# Sheet1.net
KiCad netlist of a schematic drawn in Altium Designer
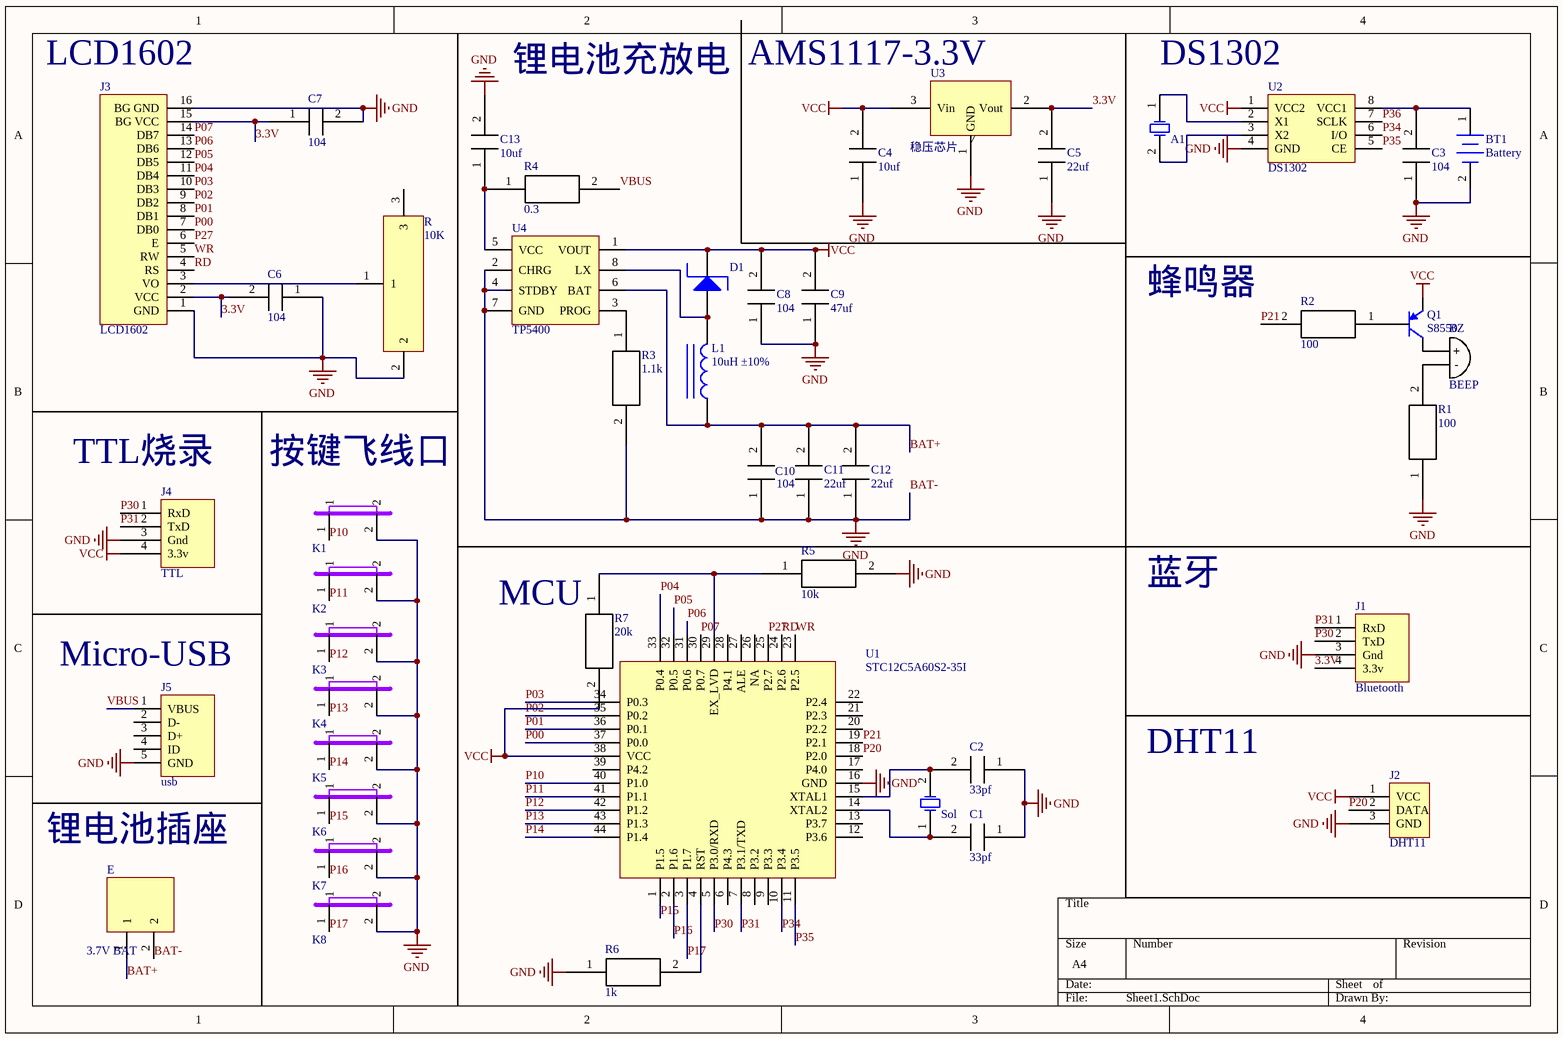
[diagram p0: Sheet1.SchDoc]

(export (version "E")
  (design (tool "Eeschema 10.0.6"))
  (components
    (comp (ref "A1")
      (value "CrystalOscillator")
      (footprint "3*8圆柱晶振")
      (description "晶振")
      (libsource (lib "Schlib1") (part "XTAL"))
    )
    (comp (ref "BT1")
      (value "Battery")
      (footprint "CR1220_A")
      (description "Multicell Battery")
      (fields (field (name "PUBLISHER") "Altium Limited"))
      (libsource (lib "Schlib1") (part "Battery"))
    )
    (comp (ref "BZ")
      (value "BEEP")
      (footprint "BEEP 6.6x12x8.5")
      (description "蜂鸣器")
      (libsource (lib "Schlib1") (part "BEEP"))
    )
    (comp (ref "C1")
      (value "33pf")
      (footprint "C 0805_M")
      (description "电容")
      (libsource (lib "Schlib1") (part "电容"))
    )
    (comp (ref "C2")
      (value "33pf")
      (footprint "C 0805_M")
      (description "电容")
      (libsource (lib "Schlib1") (part "电容"))
    )
    (comp (ref "C3")
      (value "104")
      (footprint "C 0805_M")
      (description "电容")
      (libsource (lib "Schlib1") (part "电容"))
    )
    (comp (ref "C4")
      (value "10uf")
      (footprint "C 0805_M")
      (description "电容")
      (libsource (lib "Schlib1") (part "电容"))
    )
    (comp (ref "C5")
      (value "22uf")
      (footprint "C 0805_M")
      (description "电容")
      (libsource (lib "Schlib1") (part "电容"))
    )
    (comp (ref "C6")
      (value "104")
      (footprint "C 0805_M")
      (description "电容")
      (libsource (lib "Schlib1") (part "电容"))
    )
    (comp (ref "C7")
      (value "104")
      (footprint "C 0805_M")
      (description "电容")
      (libsource (lib "Schlib1") (part "电容"))
    )
    (comp (ref "C8")
      (value "104")
      (footprint "C 0805_M")
      (description "电容")
      (libsource (lib "Schlib1") (part "电容"))
    )
    (comp (ref "C9")
      (value "47uf")
      (footprint "C 0805_M")
      (description "电容")
      (libsource (lib "Schlib1") (part "电容"))
    )
    (comp (ref "C10")
      (value "104")
      (footprint "C 0805_M")
      (description "电容")
      (libsource (lib "Schlib1") (part "电容"))
    )
    (comp (ref "C11")
      (value "22uf")
      (footprint "C 0805_M")
      (description "电容")
      (libsource (lib "Schlib1") (part "电容"))
    )
    (comp (ref "C12")
      (value "22uf")
      (footprint "C 0805_M")
      (description "电容")
      (libsource (lib "Schlib1") (part "电容"))
    )
    (comp (ref "C13")
      (value "10uf")
      (footprint "C 0805_M")
      (description "电容")
      (libsource (lib "Schlib1") (part "电容"))
    )
    (comp (ref "D1")
      (value "B5819W  SL")
      (footprint "SMB")
      (description "肖特基二极管")
      (libsource (lib "Schlib1") (part "SOD-123 B5819W  SL"))
    )
    (comp (ref "E")
      (value "3.7V BAT")
      (footprint "XH2.54-LI-2P")
      (description "电源")
      (libsource (lib "Schlib1") (part "E"))
    )
    (comp (ref "J1")
      (value "Bluetooth")
      (footprint "HDR2.54-M-LI-4P")
      (description "蓝牙")
      (libsource (lib "Schlib1") (part "BT06-B"))
    )
    (comp (ref "J2") (value "DHT11") (footprint "HDR2.54-M-LI-3P") (libsource (lib "Schlib1") (part "DHT11")))
    (comp (ref "J3") (value "LCD1602") (footprint "LCD-1602") (libsource (lib "Schlib1") (part "LCD1602")))
    (comp (ref "J4")
      (value "TTL")
      (footprint "HDR2.54-LI-4P")
      (description "蓝牙")
      (libsource (lib "Schlib1") (part "BT06-B"))
    )
    (comp (ref "J5") (value "usb") (footprint "USB-micro_C") (libsource (lib "Schlib1") (part "usb")))
    (comp (ref "K1")
      (value "key")
      (footprint "飞线口")
      (description "按键")
      (libsource (lib "Schlib1") (part "key"))
    )
    (comp (ref "K2")
      (value "key")
      (footprint "飞线口")
      (description "按键")
      (libsource (lib "Schlib1") (part "key"))
    )
    (comp (ref "K3")
      (value "key")
      (footprint "飞线口")
      (description "按键")
      (libsource (lib "Schlib1") (part "key"))
    )
    (comp (ref "K4")
      (value "key")
      (footprint "飞线口")
      (description "按键")
      (libsource (lib "Schlib1") (part "key"))
    )
    (comp (ref "K5")
      (value "key")
      (footprint "飞线口")
      (description "按键")
      (libsource (lib "Schlib1") (part "key"))
    )
    (comp (ref "K6")
      (value "key")
      (footprint "飞线口")
      (description "按键")
      (libsource (lib "Schlib1") (part "key"))
    )
    (comp (ref "K7")
      (value "key")
      (footprint "飞线口")
      (description "按键")
      (libsource (lib "Schlib1") (part "key"))
    )
    (comp (ref "K8")
      (value "key")
      (footprint "飞线口")
      (description "按键")
      (libsource (lib "Schlib1") (part "key"))
    )
    (comp (ref "L1")
      (value "10uH ±10%")
      (footprint "0805_L")
      (description "贴片电感")
      (libsource (lib "Schlib1") (part "0805 10uH 10%"))
    )
    (comp (ref "Q1")
      (value "S8550")
      (footprint "SOT23")
      (description "Discrete PNP Bipolar Transistor")
      (fields (field (name "PARTNUMBER") "S8550") (field (name "PUBLISHER") "Altium Limited"))
      (libsource (lib "Schlib1") (part "PNP S8550"))
    )
    (comp (ref "R")
      (value "10K")
      (footprint "可变电阻")
      (description "电位器")
      (libsource (lib "Schlib1") (part "3296"))
    )
    (comp (ref "R1")
      (value "100")
      (footprint "0805R")
      (description "电阻")
      (libsource (lib "Schlib1") (part "电阻"))
    )
    (comp (ref "R2")
      (value "100")
      (footprint "0805R")
      (description "电阻")
      (libsource (lib "Schlib1") (part "电阻"))
    )
    (comp (ref "R3")
      (value "1.1k")
      (footprint "0805R")
      (description "电阻")
      (libsource (lib "Schlib1") (part "电阻"))
    )
    (comp (ref "R4")
      (value "0.3")
      (footprint "0805R")
      (description "电阻")
      (libsource (lib "Schlib1") (part "电阻"))
    )
    (comp (ref "R5")
      (value "10k")
      (footprint "0805R")
      (description "电阻")
      (libsource (lib "Schlib1") (part "电阻"))
    )
    (comp (ref "R6")
      (value "1k")
      (footprint "0805R")
      (description "电阻")
      (libsource (lib "Schlib1") (part "电阻"))
    )
    (comp (ref "R7")
      (value "20k")
      (footprint "0805R")
      (description "电阻")
      (libsource (lib "Schlib1") (part "电阻"))
    )
    (comp (ref "Sol")
      (value "CrystalOscillator")
      (footprint "OSC HC-49S")
      (description "晶振")
      (libsource (lib "Schlib1") (part "XTAL"))
    )
    (comp (ref "U1")
      (value "STC12C5A60S2-35I")
      (footprint "LQFP44-10*10")
      (description "MCU")
      (libsource (lib "Schlib1") (part "STC12C5A60S2-35I"))
    )
    (comp (ref "U2")
      (value "DS1302")
      (footprint "DIP8")
      (description "DS1302时钟芯片")
      (libsource (lib "Schlib1") (part "DS1302"))
    )
    (comp (ref "U3") (value "稳压芯片") (footprint "SOT-223") (libsource (lib "Schlib1") (part "AMS1117")))
    (comp (ref "U4")
      (value "TP5400")
      (footprint "SOP8")
      (description "电池管理芯片")
      (libsource (lib "Schlib1") (part "TP5400"))
    )
  )
  (nets
    (net (code "1") (name "/3.3V") (class "Default")
      (node (ref "C5") (pin "2") (pinfunction "2_2") (pintype "passive"))
      (node (ref "C6") (pin "2") (pinfunction "2_2") (pintype "passive"))
      (node (ref "C7") (pin "1") (pinfunction "1_1") (pintype "passive"))
      (node (ref "J1") (pin "4") (pinfunction "3.3v_4") (pintype "passive"))
      (node (ref "J3") (pin "15") (pinfunction "BG_VCC_15") (pintype "passive"))
      (node (ref "J3") (pin "2") (pinfunction "VCC_2") (pintype "passive"))
      (node (ref "U3") (pin "2") (pinfunction "Vout_2") (pintype "passive"))
    )
    (net (code "2") (name "/BAT+") (class "Default")
      (node (ref "C10") (pin "2") (pinfunction "2_2") (pintype "passive"))
      (node (ref "C11") (pin "2") (pinfunction "2_2") (pintype "passive"))
      (node (ref "C12") (pin "2") (pinfunction "2_2") (pintype "passive"))
      (node (ref "E") (pin "1") (pinfunction "1_1") (pintype "passive"))
      (node (ref "L1") (pin "1") (pinfunction "1_1") (pintype "passive"))
      (node (ref "U4") (pin "6") (pinfunction "BAT_6") (pintype "passive"))
    )
    (net (code "3") (name "/P00") (class "Default")
      (node (ref "J3") (pin "7") (pinfunction "DB0_7") (pintype "passive"))
      (node (ref "U1") (pin "37") (pinfunction "P0.0_37") (pintype "passive"))
    )
    (net (code "4") (name "/P01") (class "Default")
      (node (ref "J3") (pin "8") (pinfunction "DB1_8") (pintype "passive"))
      (node (ref "U1") (pin "36") (pinfunction "P0.1_36") (pintype "passive"))
    )
    (net (code "5") (name "/P02") (class "Default")
      (node (ref "J3") (pin "9") (pinfunction "DB2_9") (pintype "passive"))
      (node (ref "U1") (pin "35") (pinfunction "P0.2_35") (pintype "passive"))
    )
    (net (code "6") (name "/P03") (class "Default")
      (node (ref "J3") (pin "10") (pinfunction "DB3_10") (pintype "passive"))
      (node (ref "U1") (pin "34") (pinfunction "P0.3_34") (pintype "passive"))
    )
    (net (code "7") (name "/P04") (class "Default")
      (node (ref "J3") (pin "11") (pinfunction "DB4_11") (pintype "passive"))
      (node (ref "U1") (pin "33") (pinfunction "P0.4_33") (pintype "passive"))
    )
    (net (code "8") (name "/P05") (class "Default")
      (node (ref "J3") (pin "12") (pinfunction "DB5_12") (pintype "passive"))
      (node (ref "U1") (pin "32") (pinfunction "P0.5_32") (pintype "passive"))
    )
    (net (code "9") (name "/P06") (class "Default")
      (node (ref "J3") (pin "13") (pinfunction "DB6_13") (pintype "passive"))
      (node (ref "U1") (pin "31") (pinfunction "P0.6_31") (pintype "passive"))
    )
    (net (code "10") (name "/P07") (class "Default")
      (node (ref "J3") (pin "14") (pinfunction "DB7_14") (pintype "passive"))
      (node (ref "U1") (pin "30") (pinfunction "P0.7_30") (pintype "passive"))
    )
    (net (code "11") (name "/P10") (class "Default")
      (node (ref "K1") (pin "1") (pinfunction "1_1") (pintype "passive"))
      (node (ref "U1") (pin "40") (pinfunction "P1.0_40") (pintype "passive"))
    )
    (net (code "12") (name "/P11") (class "Default")
      (node (ref "K2") (pin "1") (pinfunction "1_1") (pintype "passive"))
      (node (ref "U1") (pin "41") (pinfunction "P1.1_41") (pintype "passive"))
    )
    (net (code "13") (name "/P12") (class "Default")
      (node (ref "K3") (pin "1") (pinfunction "1_1") (pintype "passive"))
      (node (ref "U1") (pin "42") (pinfunction "P1.2_42") (pintype "passive"))
    )
    (net (code "14") (name "/P13") (class "Default")
      (node (ref "K4") (pin "1") (pinfunction "1_1") (pintype "passive"))
      (node (ref "U1") (pin "43") (pinfunction "P1.3_43") (pintype "passive"))
    )
    (net (code "15") (name "/P14") (class "Default")
      (node (ref "K5") (pin "1") (pinfunction "1_1") (pintype "passive"))
      (node (ref "U1") (pin "44") (pinfunction "P1.4_44") (pintype "passive"))
    )
    (net (code "16") (name "/P15") (class "Default")
      (node (ref "K6") (pin "1") (pinfunction "1_1") (pintype "passive"))
      (node (ref "U1") (pin "1") (pinfunction "P1.5_1") (pintype "passive"))
    )
    (net (code "17") (name "/P16") (class "Default")
      (node (ref "K7") (pin "1") (pinfunction "1_1") (pintype "passive"))
      (node (ref "U1") (pin "2") (pinfunction "P1.6_2") (pintype "passive"))
    )
    (net (code "18") (name "/P17") (class "Default")
      (node (ref "K8") (pin "1") (pinfunction "1_1") (pintype "passive"))
      (node (ref "U1") (pin "3") (pinfunction "P1.7_3") (pintype "passive"))
    )
    (net (code "19") (name "/P20") (class "Default")
      (node (ref "J2") (pin "2") (pinfunction "DATA_2") (pintype "passive"))
      (node (ref "U1") (pin "18") (pinfunction "P2.0_18") (pintype "passive"))
    )
    (net (code "20") (name "/P21") (class "Default")
      (node (ref "R2") (pin "2") (pinfunction "2_2") (pintype "passive"))
      (node (ref "U1") (pin "19") (pinfunction "P2.1_19") (pintype "passive"))
    )
    (net (code "21") (name "/P27") (class "Default")
      (node (ref "J3") (pin "6") (pinfunction "E_6") (pintype "passive"))
      (node (ref "U1") (pin "25") (pinfunction "P2.7_25") (pintype "passive"))
    )
    (net (code "22") (name "/P30") (class "Default")
      (node (ref "J1") (pin "2") (pinfunction "TxD_2") (pintype "passive"))
      (node (ref "J4") (pin "1") (pinfunction "RxD_1") (pintype "passive"))
      (node (ref "U1") (pin "5") (pinfunction "P3.0/RXD_5") (pintype "passive"))
    )
    (net (code "23") (name "/P31") (class "Default")
      (node (ref "J1") (pin "1") (pinfunction "RxD_1") (pintype "passive"))
      (node (ref "J4") (pin "2") (pinfunction "TxD_2") (pintype "passive"))
      (node (ref "U1") (pin "7") (pinfunction "P3.1/TXD_7") (pintype "passive"))
    )
    (net (code "24") (name "/P34") (class "Default")
      (node (ref "U1") (pin "10") (pinfunction "P3.4_10") (pintype "passive"))
      (node (ref "U2") (pin "6") (pinfunction "I/O_6") (pintype "passive"))
    )
    (net (code "25") (name "/P35") (class "Default")
      (node (ref "U1") (pin "11") (pinfunction "P3.5_11") (pintype "passive"))
      (node (ref "U2") (pin "5") (pinfunction "CE_5") (pintype "passive"))
    )
    (net (code "26") (name "/P36") (class "Default")
      (node (ref "U2") (pin "7") (pinfunction "SCLK_7") (pintype "passive"))
    )
    (net (code "27") (name "/RD") (class "Default")
      (node (ref "J3") (pin "4") (pinfunction "RS_4") (pintype "passive"))
      (node (ref "U1") (pin "24") (pinfunction "P2.6_24") (pintype "passive"))
    )
    (net (code "28") (name "/VBUS") (class "Default")
      (node (ref "J5") (pin "1") (pinfunction "VBUS_1") (pintype "passive"))
      (node (ref "R4") (pin "2") (pinfunction "2_2") (pintype "passive"))
    )
    (net (code "29") (name "/WR") (class "Default")
      (node (ref "J3") (pin "5") (pinfunction "RW_5") (pintype "passive"))
      (node (ref "U1") (pin "23") (pinfunction "P2.5_23") (pintype "passive"))
    )
    (net (code "30") (name "GND") (class "Default")
      (node (ref "BT1") (pin "2") (pinfunction "-_2") (pintype "passive"))
      (node (ref "C1") (pin "1") (pinfunction "1_1") (pintype "passive"))
      (node (ref "C10") (pin "1") (pinfunction "1_1") (pintype "passive"))
      (node (ref "C11") (pin "1") (pinfunction "1_1") (pintype "passive"))
      (node (ref "C12") (pin "1") (pinfunction "1_1") (pintype "passive"))
      (node (ref "C13") (pin "2") (pinfunction "2_2") (pintype "passive"))
      (node (ref "C2") (pin "1") (pinfunction "1_1") (pintype "passive"))
      (node (ref "C3") (pin "1") (pinfunction "1_1") (pintype "passive"))
      (node (ref "C4") (pin "1") (pinfunction "1_1") (pintype "passive"))
      (node (ref "C5") (pin "1") (pinfunction "1_1") (pintype "passive"))
      (node (ref "C6") (pin "1") (pinfunction "1_1") (pintype "passive"))
      (node (ref "C7") (pin "2") (pinfunction "2_2") (pintype "passive"))
      (node (ref "C8") (pin "1") (pinfunction "1_1") (pintype "passive"))
      (node (ref "C9") (pin "1") (pinfunction "1_1") (pintype "passive"))
      (node (ref "E") (pin "2") (pinfunction "2_2") (pintype "passive"))
      (node (ref "J1") (pin "3") (pinfunction "Gnd_3") (pintype "passive"))
      (node (ref "J2") (pin "3") (pinfunction "GND_3") (pintype "passive"))
      (node (ref "J3") (pin "1") (pinfunction "GND_1") (pintype "passive"))
      (node (ref "J3") (pin "16") (pinfunction "BG_GND_16") (pintype "passive"))
      (node (ref "J4") (pin "3") (pinfunction "Gnd_3") (pintype "passive"))
      (node (ref "J5") (pin "5") (pinfunction "GND_5") (pintype "passive"))
      (node (ref "K1") (pin "2") (pinfunction "2_2") (pintype "passive"))
      (node (ref "K2") (pin "2") (pinfunction "2_2") (pintype "passive"))
      (node (ref "K3") (pin "2") (pinfunction "2_2") (pintype "passive"))
      (node (ref "K4") (pin "2") (pinfunction "2_2") (pintype "passive"))
      (node (ref "K5") (pin "2") (pinfunction "2_2") (pintype "passive"))
      (node (ref "K6") (pin "2") (pinfunction "2_2") (pintype "passive"))
      (node (ref "K7") (pin "2") (pinfunction "2_2") (pintype "passive"))
      (node (ref "K8") (pin "2") (pinfunction "2_2") (pintype "passive"))
      (node (ref "R") (pin "2") (pinfunction "2_2") (pintype "passive"))
      (node (ref "R1") (pin "1") (pinfunction "1_1") (pintype "passive"))
      (node (ref "R3") (pin "2") (pinfunction "2_2") (pintype "passive"))
      (node (ref "R5") (pin "2") (pinfunction "2_2") (pintype "passive"))
      (node (ref "R6") (pin "1") (pinfunction "1_1") (pintype "passive"))
      (node (ref "U1") (pin "16") (pinfunction "GND_16") (pintype "power_in"))
      (node (ref "U2") (pin "4") (pinfunction "GND_4") (pintype "passive"))
      (node (ref "U3") (pin "1") (pinfunction "GND_1") (pintype "passive"))
      (node (ref "U4") (pin "2") (pinfunction "CHRG_2") (pintype "passive"))
      (node (ref "U4") (pin "4") (pinfunction "STDBY_4") (pintype "passive"))
      (node (ref "U4") (pin "7") (pinfunction "GND_7") (pintype "passive"))
    )
    (net (code "31") (name "Net-(A1-OSC1)") (class "Default")
      (node (ref "A1") (pin "1") (pinfunction "OSC1_1") (pintype "passive"))
      (node (ref "U2") (pin "2") (pinfunction "X1_2") (pintype "passive"))
    )
    (net (code "32") (name "Net-(A1-OSC2)") (class "Default")
      (node (ref "A1") (pin "2") (pinfunction "OSC2_2") (pintype "passive"))
      (node (ref "U2") (pin "3") (pinfunction "X2_3") (pintype "passive"))
    )
    (net (code "33") (name "Net-(BT1-+)") (class "Default")
      (node (ref "BT1") (pin "1") (pinfunction "+_1") (pintype "passive"))
      (node (ref "C3") (pin "2") (pinfunction "2_2") (pintype "passive"))
      (node (ref "U2") (pin "8") (pinfunction "VCC1_8") (pintype "passive"))
    )
    (net (code "34") (name "Net-(BZ-+)") (class "Default")
      (node (ref "BZ") (pin "1") (pinfunction "+_1") (pintype "passive"))
      (node (ref "Q1") (pin "3") (pinfunction "C_3") (pintype "passive"))
    )
    (net (code "35") (name "Net-(BZ--)") (class "Default")
      (node (ref "BZ") (pin "2") (pinfunction "-_2") (pintype "passive"))
      (node (ref "R1") (pin "2") (pinfunction "2_2") (pintype "passive"))
    )
    (net (code "36") (name "Net-(D1-A)") (class "Default")
      (node (ref "D1") (pin "1") (pinfunction "A_1") (pintype "passive"))
      (node (ref "L1") (pin "2") (pinfunction "2_2") (pintype "passive"))
      (node (ref "U4") (pin "8") (pinfunction "LX_8") (pintype "passive"))
    )
    (net (code "37") (name "Net-(J3-VO)") (class "Default")
      (node (ref "J3") (pin "3") (pinfunction "VO_3") (pintype "passive"))
      (node (ref "R") (pin "1") (pinfunction "1_1") (pintype "passive"))
    )
    (net (code "38") (name "Net-(Q1-B)") (class "Default")
      (node (ref "Q1") (pin "1") (pinfunction "B_1") (pintype "passive"))
      (node (ref "R2") (pin "1") (pinfunction "1_1") (pintype "passive"))
    )
    (net (code "39") (name "Net-(Sol-OSC1)") (class "Default")
      (node (ref "C1") (pin "2") (pinfunction "2_2") (pintype "passive"))
      (node (ref "Sol") (pin "1") (pinfunction "OSC1_1") (pintype "passive"))
      (node (ref "U1") (pin "14") (pinfunction "XTAL2_14") (pintype "passive"))
    )
    (net (code "40") (name "Net-(Sol-OSC2)") (class "Default")
      (node (ref "C2") (pin "2") (pinfunction "2_2") (pintype "passive"))
      (node (ref "Sol") (pin "2") (pinfunction "OSC2_2") (pintype "passive"))
      (node (ref "U1") (pin "15") (pinfunction "XTAL1_15") (pintype "passive"))
    )
    (net (code "41") (name "Net-(U1-EX_LVD)") (class "Default")
      (node (ref "R5") (pin "1") (pinfunction "1_1") (pintype "passive"))
      (node (ref "R7") (pin "1") (pinfunction "1_1") (pintype "passive"))
      (node (ref "U1") (pin "29") (pinfunction "EX_LVD_29") (pintype "passive"))
    )
    (net (code "42") (name "Net-(U1-RST)") (class "Default")
      (node (ref "R6") (pin "2") (pinfunction "2_2") (pintype "passive"))
      (node (ref "U1") (pin "4") (pinfunction "RST_4") (pintype "passive"))
    )
    (net (code "43") (name "Net-(U4-PROG)") (class "Default")
      (node (ref "R3") (pin "1") (pinfunction "1_1") (pintype "passive"))
      (node (ref "U4") (pin "3") (pinfunction "PROG_3") (pintype "passive"))
    )
    (net (code "44") (name "Net-(U4-VCC)") (class "Default")
      (node (ref "C13") (pin "1") (pinfunction "1_1") (pintype "passive"))
      (node (ref "R4") (pin "1") (pinfunction "1_1") (pintype "passive"))
      (node (ref "U4") (pin "5") (pinfunction "VCC_5") (pintype "passive"))
    )
    (net (code "45") (name "VCC") (class "Default")
      (node (ref "C4") (pin "2") (pinfunction "2_2") (pintype "passive"))
      (node (ref "C8") (pin "2") (pinfunction "2_2") (pintype "passive"))
      (node (ref "C9") (pin "2") (pinfunction "2_2") (pintype "passive"))
      (node (ref "D1") (pin "2") (pinfunction "K_2") (pintype "passive"))
      (node (ref "J2") (pin "1") (pinfunction "VCC_1") (pintype "passive"))
      (node (ref "J4") (pin "4") (pinfunction "3.3v_4") (pintype "passive"))
      (node (ref "Q1") (pin "2") (pinfunction "E_2") (pintype "passive"))
      (node (ref "R7") (pin "2") (pinfunction "2_2") (pintype "passive"))
      (node (ref "U1") (pin "38") (pinfunction "VCC_38") (pintype "power_in"))
      (node (ref "U2") (pin "1") (pinfunction "VCC2_1") (pintype "passive"))
      (node (ref "U3") (pin "3") (pinfunction "Vin_3") (pintype "passive"))
      (node (ref "U4") (pin "1") (pinfunction "VOUT_1") (pintype "passive"))
    )
    (net (code "46") (name "unconnected-(J5-D+-Pad3)") (class "Default")
      (node (ref "J5") (pin "3") (pinfunction "D+_3") (pintype "passive"))
    )
    (net (code "47") (name "unconnected-(J5-D--Pad2)") (class "Default")
      (node (ref "J5") (pin "2") (pinfunction "D-_2") (pintype "passive"))
    )
    (net (code "48") (name "unconnected-(J5-ID-Pad4)") (class "Default")
      (node (ref "J5") (pin "4") (pinfunction "ID_4") (pintype "passive"))
    )
    (net (code "49") (name "unconnected-(R-Pad3)") (class "Default")
      (node (ref "R") (pin "3") (pinfunction "3_3") (pintype "passive"))
    )
    (net (code "50") (name "unconnected-(U1-ALE-Pad27)") (class "Default")
      (node (ref "U1") (pin "27") (pinfunction "ALE_27") (pintype "passive"))
    )
    (net (code "51") (name "unconnected-(U1-NA-Pad26)") (class "Default")
      (node (ref "U1") (pin "26") (pinfunction "NA_26") (pintype "passive"))
    )
    (net (code "52") (name "unconnected-(U1-P2.2-Pad20)") (class "Default")
      (node (ref "U1") (pin "20") (pinfunction "P2.2_20") (pintype "passive"))
    )
    (net (code "53") (name "unconnected-(U1-P2.3-Pad21)") (class "Default")
      (node (ref "U1") (pin "21") (pinfunction "P2.3_21") (pintype "passive"))
    )
    (net (code "54") (name "unconnected-(U1-P2.4-Pad22)") (class "Default")
      (node (ref "U1") (pin "22") (pinfunction "P2.4_22") (pintype "passive"))
    )
    (net (code "55") (name "unconnected-(U1-P3.2-Pad8)") (class "Default")
      (node (ref "U1") (pin "8") (pinfunction "P3.2_8") (pintype "passive"))
    )
    (net (code "56") (name "unconnected-(U1-P3.3-Pad9)") (class "Default")
      (node (ref "U1") (pin "9") (pinfunction "P3.3_9") (pintype "passive"))
    )
    (net (code "57") (name "unconnected-(U1-P3.6-Pad12)") (class "Default")
      (node (ref "U1") (pin "12") (pinfunction "P3.6_12") (pintype "passive"))
    )
    (net (code "58") (name "unconnected-(U1-P3.7-Pad13)") (class "Default")
      (node (ref "U1") (pin "13") (pinfunction "P3.7_13") (pintype "passive"))
    )
    (net (code "59") (name "unconnected-(U1-P4.0-Pad17)") (class "Default")
      (node (ref "U1") (pin "17") (pinfunction "P4.0_17") (pintype "passive"))
    )
    (net (code "60") (name "unconnected-(U1-P4.1-Pad28)") (class "Default")
      (node (ref "U1") (pin "28") (pinfunction "P4.1_28") (pintype "passive"))
    )
    (net (code "61") (name "unconnected-(U1-P4.2-Pad39)") (class "Default")
      (node (ref "U1") (pin "39") (pinfunction "P4.2_39") (pintype "passive"))
    )
    (net (code "62") (name "unconnected-(U1-P4.3-Pad6)") (class "Default")
      (node (ref "U1") (pin "6") (pinfunction "P4.3_6") (pintype "passive"))
    )
  )
)
